# sheet.net
KiCad netlist of a schematic drawn in Altium Designer
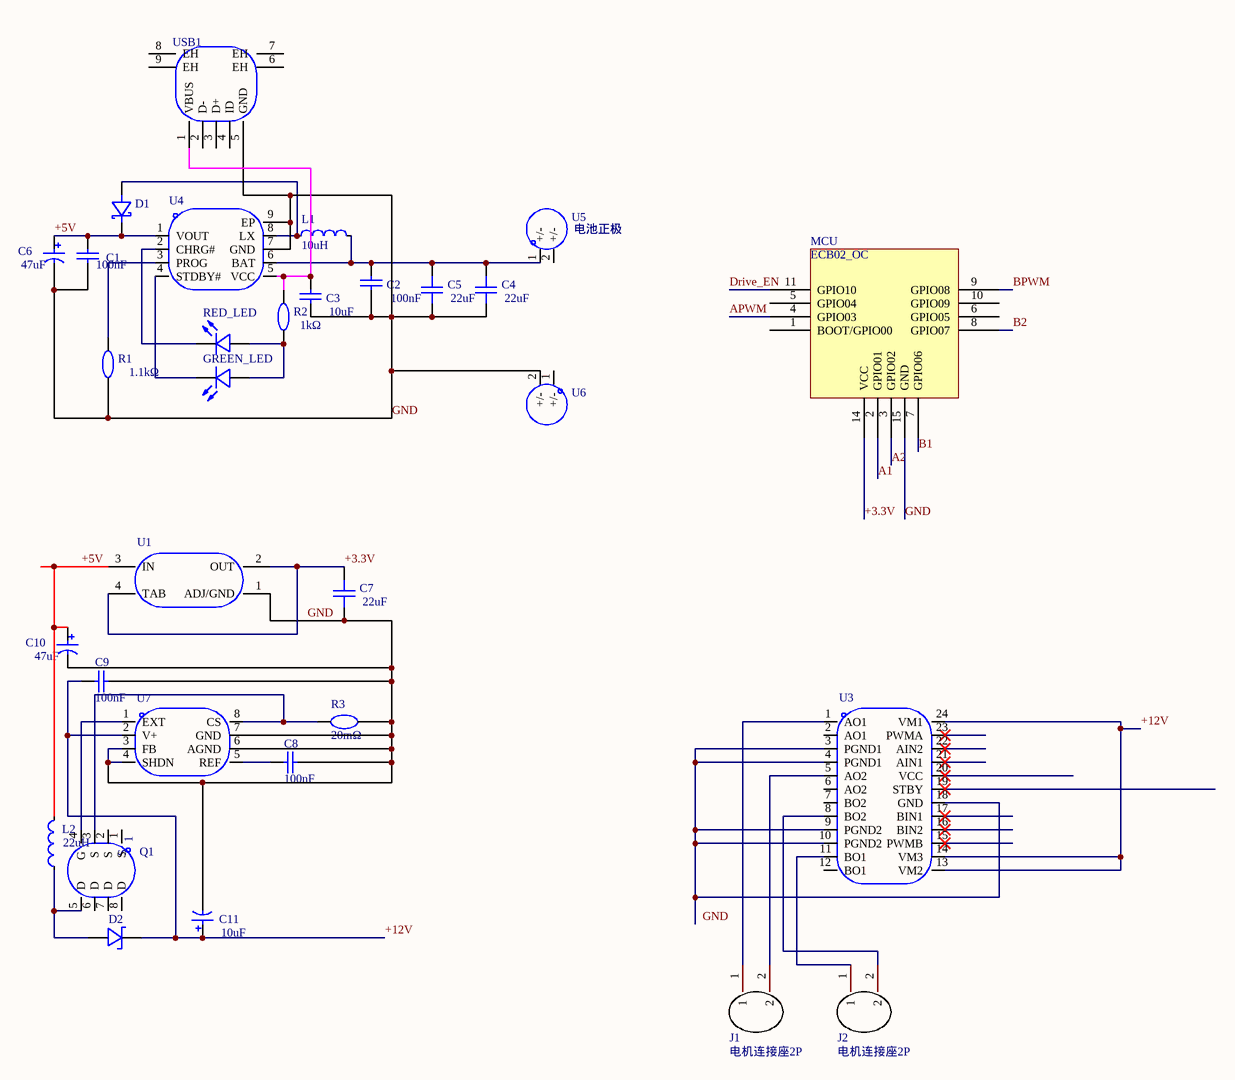
[diagram p0: sheet.schdoc]

(export (version "E")
  (design (tool "Eeschema 10.0.6"))
  (components
    (comp (ref "C1")
      (value "100nF")
      (footprint "C1206")
      (fields
        (field (name "MANUFACTURER") "FH(风华)")
        (field (name "MANUFACTURER PART") "1206B104K500NT")
        (field (name "TOLERANCE") "±10%")
      )
      (libsource (lib "altium-import") (part "root_1_1206B104K500NT_"))
    )
    (comp (ref "C2")
      (value "100nF")
      (footprint "C1206")
      (fields
        (field (name "MANUFACTURER") "FH(风华)")
        (field (name "MANUFACTURER PART") "1206B104K500NT")
        (field (name "TOLERANCE") "±10%")
      )
      (libsource (lib "altium-import") (part "root_1_1206B104K500NT_"))
    )
    (comp (ref "C3")
      (value "10uF")
      (footprint "C1206")
      (fields
        (field (name "MANUFACTURER") "SAMSUNG(三星)")
        (field (name "MANUFACTURER PART") "CL31B106KOHNNNE")
        (field (name "TOLERANCE") "±10%")
      )
      (libsource (lib "altium-import") (part "root_1_CL31B106KOHNNNE_"))
    )
    (comp (ref "C4")
      (value "22uF")
      (footprint "C1206")
      (fields
        (field (name "MANUFACTURER") "SAMSUNG(三星)")
        (field (name "MANUFACTURER PART") "CL31A226KOHNNNE")
        (field (name "TOLERANCE") "±10%")
      )
      (libsource (lib "altium-import") (part "root_1_CL31A226KOHNNNE_"))
    )
    (comp (ref "C5")
      (value "22uF")
      (footprint "C1206")
      (fields
        (field (name "MANUFACTURER") "SAMSUNG(三星)")
        (field (name "MANUFACTURER PART") "CL31A226KOHNNNE")
        (field (name "TOLERANCE") "±10%")
      )
      (libsource (lib "altium-import") (part "root_1_CL31A226KOHNNNE_"))
    )
    (comp (ref "C6")
      (value "47uF")
      (footprint "CAP-TH_BD5.0-P2.00-D0.8-FD")
      (fields
        (field (name "MANUFACTURER") "rubycon(红宝石)")
        (field (name "MANUFACTURER PART") "25YXF47MEFC5X11")
        (field (name "TOLERANCE") "±20%")
      )
      (libsource (lib "altium-import") (part "root_3_25YXF47MEFC5X11_"))
    )
    (comp (ref "C7")
      (value "22uF")
      (footprint "C1206")
      (fields
        (field (name "MANUFACTURER") "SAMSUNG(三星)")
        (field (name "MANUFACTURER PART") "CL31A226KOHNNNE")
        (field (name "TOLERANCE") "±10%")
      )
      (libsource (lib "altium-import") (part "root_1_CL31A226KOHNNNE_"))
    )
    (comp (ref "C8")
      (value "100nF")
      (footprint "C1206")
      (fields
        (field (name "MANUFACTURER") "FH(风华)")
        (field (name "MANUFACTURER PART") "1206B104K500NT")
        (field (name "TOLERANCE") "±10%")
      )
      (libsource (lib "altium-import") (part "root_2_1206B104K500NT_"))
    )
    (comp (ref "C9")
      (value "100nF")
      (footprint "C1206")
      (fields
        (field (name "MANUFACTURER") "FH(风华)")
        (field (name "MANUFACTURER PART") "1206B104K500NT")
        (field (name "TOLERANCE") "±10%")
      )
      (libsource (lib "altium-import") (part "root_2_1206B104K500NT_"))
    )
    (comp (ref "C10")
      (value "47uF")
      (footprint "CAP-TH_BD5.0-P2.00-D0.8-FD")
      (fields
        (field (name "MANUFACTURER") "rubycon(红宝石)")
        (field (name "MANUFACTURER PART") "25YXF47MEFC5X11")
        (field (name "TOLERANCE") "±20%")
      )
      (libsource (lib "altium-import") (part "root_3_25YXF47MEFC5X11_"))
    )
    (comp (ref "C11")
      (value "10uF")
      (footprint "CAP-TH_BD5.0-P2.00-D0.8-FD")
      (fields
        (field (name "MANUFACTURER") "rubycon(红宝石)")
        (field (name "MANUFACTURER PART") "50YXF10MEFC5X11")
        (field (name "TOLERANCE") "±20%")
      )
      (libsource (lib "altium-import") (part "root_1_50YXF10MEFC5X11_"))
    )
    (comp (ref "D1")
      (value "~")
      (footprint "SMA_L4.3-W2.6-LS5.1-RD")
      (fields (field (name "MANUFACTURER") "Slkor(萨科微)") (field (name "MANUFACTURER PART") "SS32"))
      (libsource (lib "altium-import") (part "root_1_SS32_C5122584_"))
    )
    (comp (ref "D2")
      (value "~")
      (footprint "SOD-323_L1.8-W1.3-LS2.5-RD")
      (fields (field (name "MANUFACTURER") "Hottech(合科泰)") (field (name "MANUFACTURER PART") "1N5819WS"))
      (libsource (lib "altium-import") (part "root_2_1N5819WS_C191023_"))
    )
    (comp (ref "GREEN_LED")
      (value "~")
      (footprint "LED0805-R-RD")
      (fields (field (name "MANUFACTURER") "国星光电") (field (name "MANUFACTURER PART") "NCD0805G1"))
      (libsource (lib "altium-import") (part "root_2_NCD0805G1_"))
    )
    (comp (ref "J1") (value "电机连接座2P") (footprint "电机连接座2P") (libsource (lib "1_P1") (part "电机连接座2P")))
    (comp (ref "J2") (value "电机连接座2P") (footprint "电机连接座2P") (libsource (lib "1_P1") (part "电机连接座2P")))
    (comp (ref "L1")
      (value "10uH")
      (footprint "IND-SMD_L4.4-W4.2")
      (fields
        (field (name "MANUFACTURER") "cjiang(长江微电)")
        (field (name "MANUFACTURER PART") "FXL0420-100-M")
        (field (name "TOLERANCE") "±20%")
      )
      (libsource (lib "altium-import") (part "root_0_FXL0420-100-M_"))
    )
    (comp (ref "L2")
      (value "22uH")
      (footprint "IND-SMD_L6.0-W6.0_SWPA6045S")
      (fields
        (field (name "MANUFACTURER") "Sunlord(顺络)")
        (field (name "MANUFACTURER PART") "SWPA6045S220MT")
        (field (name "TOLERANCE") "±20%")
      )
      (libsource (lib "altium-import") (part "root_1_SWPA6045S220MT_"))
    )
    (comp (ref "MCU") (value "ECB02_OC") (footprint "ECB02_OC") (libsource (lib "1_P1") (part "ECB02_OC")))
    (comp (ref "Q1")
      (value "~")
      (footprint "SO-8_L4.9-W3.9-P1.27-LS5.9-BL")
      (fields
        (field (name "MANUFACTURER") "VBsemi(台湾微碧)")
        (field (name "MANUFACTURER PART") "SI9410BDY-T1")
        (field (name "NAME") "S")
        (field (name "NUMBER") "1")
      )
      (libsource (lib "altium-import") (part "root_3_SI9410BDY-T1_"))
    )
    (comp (ref "R1")
      (value "1.1kΩ")
      (footprint "R1206")
      (fields
        (field (name "MANUFACTURER") "RESI(开步睿思）")
        (field (name "MANUFACTURER PART") "AECR1206F1K10K9")
        (field (name "TOLERANCE") "±1%")
      )
      (libsource (lib "altium-import") (part "root_1_AECR1206F1K10K9_"))
    )
    (comp (ref "R2")
      (value "1kΩ")
      (footprint "R1206")
      (fields
        (field (name "MANUFACTURER") "UNI-ROYAL(厚声)")
        (field (name "MANUFACTURER PART") "1206W4J0102T5E")
        (field (name "TOLERANCE") "±5%")
      )
      (libsource (lib "altium-import") (part "root_1_1206W4J0102T5E_"))
    )
    (comp (ref "R3")
      (value "20mΩ")
      (footprint "R1206")
      (fields
        (field (name "MANUFACTURER") "UNI-ROYAL(厚声)")
        (field (name "MANUFACTURER PART") "1206W3F200MT5E")
        (field (name "TOLERANCE") "±1%")
      )
      (libsource (lib "altium-import") (part "root_0_1206W3F200MT5E_"))
    )
    (comp (ref "RED_LED")
      (value "~")
      (footprint "LED0805-RD_RED")
      (fields (field (name "MANUFACTURER") "国星光电") (field (name "MANUFACTURER PART") "NCD0805R1"))
      (libsource (lib "altium-import") (part "root_0_NCD0805R1_"))
    )
    (comp (ref "U1")
      (value "~")
      (footprint "TO-263-3L_L10.0-W9.2-P2.54-TL")
      (fields (field (name "MANUFACTURER") "HTC") (field (name "MANUFACTURER PART") "LM1085R-3.3"))
      (libsource (lib "altium-import") (part "root_0_LM1085R-3.3_"))
    )
    (comp (ref "U3")
      (value "~")
      (footprint "SSOP-24_L8.4-W5.8-P0.65-LS7.8-BL")
      (fields
        (field (name "MANUFACTURER") "TOSHIBA(东芝)")
        (field (name "MANUFACTURER PART") "TB6612FNG(O,C,8,EL")
      )
      (libsource (lib "altium-import") (part "root_0_TB6612FNG(O,C,8,EL_"))
    )
    (comp (ref "U4")
      (value "~")
      (footprint "ESOP-8_L4.9-W3.9-P1.27-LS6.0-BL-EP")
      (fields (field (name "MANUFACTURER") "TOPPOWER(南京拓微)") (field (name "MANUFACTURER PART") "TP5400"))
      (libsource (lib "altium-import") (part "root_0_TP5400_"))
    )
    (comp (ref "U5")
      (value "电池正极")
      (footprint "BAT-SMD_MY-18650-02")
      (fields
        (field (name "NAME") "电池正极")
        (field (name "MANUFACTURER") "MYOUNG(美阳)")
        (field (name "MANUFACTURER PART") "MY-18650-02")
      )
      (libsource (lib "altium-import") (part "root_1_MY-18650-02_"))
    )
    (comp (ref "U6")
      (value "电池负极")
      (footprint "BAT-SMD_MY-18650-02")
      (fields (field (name "MANUFACTURER") "MYOUNG(美阳)") (field (name "MANUFACTURER PART") "MY-18650-02"))
      (libsource (lib "altium-import") (part "root_3_MY-18650-02_"))
    )
    (comp (ref "U7")
      (value "~")
      (footprint "SO-8_L4.9-W3.9-P1.27-LS6.0-BL")
      (fields (field (name "MANUFACTURER") "MAXIM(美信)") (field (name "MANUFACTURER PART") "MAX1771ESA+T"))
      (libsource (lib "altium-import") (part "root_0_MAX1771ESA+T_"))
    )
    (comp (ref "USB1")
      (value "~")
      (footprint "MICRO-USB-SMD_KH-MICRO-SMT.ZJ-5P")
      (fields
        (field (name "MANUFACTURER") "kinghelm(金航标)")
        (field (name "MANUFACTURER PART") "KH-MICRO-SMT.ZJ-5P")
      )
      (libsource (lib "altium-import") (part "root_1_KH-MICRO-SMT.ZJ-5P_"))
    )
  )
  (nets
    (net (code "1") (name "/+3.3V") (class "Default")
      (node (ref "C7") (pin "2") (pinfunction "2_2") (pintype "passive"))
      (node (ref "MCU") (pin "14") (pinfunction "VCC_14") (pintype "passive"))
      (node (ref "U1") (pin "2") (pinfunction "OUT_2") (pintype "passive"))
      (node (ref "U1") (pin "4") (pinfunction "TAB_4") (pintype "passive"))
    )
    (net (code "2") (name "/+5V") (class "Default")
      (node (ref "C1") (pin "2") (pinfunction "2_2") (pintype "passive"))
      (node (ref "C10") (pin "1") (pinfunction "1_1") (pintype "passive"))
      (node (ref "C6") (pin "1") (pinfunction "1_1") (pintype "passive"))
      (node (ref "D1") (pin "1") (pinfunction "1_1") (pintype "passive"))
      (node (ref "L2") (pin "2") (pinfunction "2_2") (pintype "passive"))
      (node (ref "U1") (pin "3") (pinfunction "IN_3") (pintype "passive"))
      (node (ref "U4") (pin "1") (pinfunction "VOUT_1") (pintype "passive"))
    )
    (net (code "3") (name "/+12V") (class "Default")
      (node (ref "C11") (pin "1") (pinfunction "1_1") (pintype "passive"))
      (node (ref "C9") (pin "2") (pinfunction "2_2") (pintype "passive"))
      (node (ref "D2") (pin "1") (pinfunction "C_1") (pintype "passive"))
      (node (ref "U3") (pin "13") (pinfunction "VM2_13") (pintype "passive"))
      (node (ref "U3") (pin "14") (pinfunction "VM3_14") (pintype "passive"))
      (node (ref "U3") (pin "24") (pinfunction "VM1_24") (pintype "passive"))
      (node (ref "U7") (pin "2") (pinfunction "V+_2") (pintype "passive"))
    )
    (net (code "4") (name "/A1") (class "Default")
      (node (ref "MCU") (pin "2") (pinfunction "GPIO01_2") (pintype "passive"))
    )
    (net (code "5") (name "/A2") (class "Default")
      (node (ref "MCU") (pin "3") (pinfunction "GPIO02_3") (pintype "passive"))
    )
    (net (code "6") (name "/APWM") (class "Default")
      (node (ref "MCU") (pin "4") (pinfunction "GPIO03_4") (pintype "passive"))
    )
    (net (code "7") (name "/B1") (class "Default")
      (node (ref "MCU") (pin "7") (pinfunction "GPIO06_7") (pintype "passive"))
    )
    (net (code "8") (name "/B2") (class "Default")
      (node (ref "MCU") (pin "8") (pinfunction "GPIO07_8") (pintype "passive"))
    )
    (net (code "9") (name "/BPWM") (class "Default")
      (node (ref "MCU") (pin "9") (pinfunction "GPIO08_9") (pintype "passive"))
    )
    (net (code "10") (name "/Drive_EN") (class "Default")
      (node (ref "MCU") (pin "11") (pinfunction "GPIO10_11") (pintype "passive"))
    )
    (net (code "11") (name "/GND") (class "Default")
      (node (ref "C1") (pin "1") (pinfunction "1_1") (pintype "passive"))
      (node (ref "C10") (pin "2") (pinfunction "2_2") (pintype "passive"))
      (node (ref "C11") (pin "2") (pinfunction "2_2") (pintype "passive"))
      (node (ref "C2") (pin "1") (pinfunction "1_1") (pintype "passive"))
      (node (ref "C3") (pin "1") (pinfunction "1_1") (pintype "passive"))
      (node (ref "C4") (pin "1") (pinfunction "1_1") (pintype "passive"))
      (node (ref "C5") (pin "1") (pinfunction "1_1") (pintype "passive"))
      (node (ref "C6") (pin "2") (pinfunction "2_2") (pintype "passive"))
      (node (ref "C7") (pin "1") (pinfunction "1_1") (pintype "passive"))
      (node (ref "C8") (pin "1") (pinfunction "1_1") (pintype "passive"))
      (node (ref "C9") (pin "1") (pinfunction "1_1") (pintype "passive"))
      (node (ref "MCU") (pin "15") (pinfunction "GND_15") (pintype "passive"))
      (node (ref "R1") (pin "1") (pinfunction "1_1") (pintype "passive"))
      (node (ref "R3") (pin "2") (pinfunction "2_2") (pintype "passive"))
      (node (ref "U1") (pin "1") (pinfunction "ADJ/GND_1") (pintype "passive"))
      (node (ref "U4") (pin "7") (pinfunction "GND_7") (pintype "passive"))
      (node (ref "U4") (pin "9") (pinfunction "EP_9") (pintype "passive"))
      (node (ref "U6") (pin "2") (pinfunction "+/-_2") (pintype "passive"))
      (node (ref "U7") (pin "3") (pinfunction "FB_3") (pintype "passive"))
      (node (ref "U7") (pin "4") (pinfunction "SHDN_4") (pintype "passive"))
      (node (ref "U7") (pin "6") (pinfunction "AGND_6") (pintype "passive"))
      (node (ref "U7") (pin "7") (pinfunction "GND_7") (pintype "passive"))
      (node (ref "USB1") (pin "5") (pinfunction "GND_5") (pintype "passive"))
    )
    (net (code "12") (name "Net-(D2-A)") (class "Default")
      (node (ref "D2") (pin "2") (pinfunction "A_2") (pintype "passive"))
      (node (ref "L2") (pin "1") (pinfunction "1_1") (pintype "passive"))
      (node (ref "Q1") (pin "5") (pinfunction "D_5") (pintype "passive"))
    )
    (net (code "13") (name "Net-(GREEN_LED-A)") (class "Default")
      (node (ref "GREEN_LED") (pin "1") (pinfunction "A_1") (pintype "passive"))
      (node (ref "R2") (pin "1") (pinfunction "1_1") (pintype "passive"))
      (node (ref "RED_LED") (pin "2") (pinfunction "+_2") (pintype "passive"))
    )
    (net (code "14") (name "Net-(GREEN_LED-K)") (class "Default")
      (node (ref "GREEN_LED") (pin "2") (pinfunction "K_2") (pintype "passive"))
      (node (ref "U4") (pin "4") (pinfunction "STDBY#_4") (pintype "passive"))
    )
    (net (code "15") (name "Net-(J1-Pad1)") (class "Default")
      (node (ref "J1") (pin "1") (pinfunction "1_1") (pintype "passive"))
      (node (ref "U3") (pin "1") (pinfunction "AO1_1") (pintype "passive"))
    )
    (net (code "16") (name "Net-(J1-Pad2)") (class "Default")
      (node (ref "J1") (pin "2") (pinfunction "2_2") (pintype "passive"))
      (node (ref "U3") (pin "5") (pinfunction "AO2_5") (pintype "passive"))
    )
    (net (code "17") (name "Net-(J2-Pad1)") (class "Default")
      (node (ref "J2") (pin "1") (pinfunction "1_1") (pintype "passive"))
      (node (ref "U3") (pin "11") (pinfunction "BO1_11") (pintype "passive"))
    )
    (net (code "18") (name "Net-(J2-Pad2)") (class "Default")
      (node (ref "J2") (pin "2") (pinfunction "2_2") (pintype "passive"))
      (node (ref "U3") (pin "8") (pinfunction "BO2_8") (pintype "passive"))
    )
    (net (code "19") (name "Net-(Q1-G)") (class "Default")
      (node (ref "Q1") (pin "4") (pinfunction "G_4") (pintype "passive"))
      (node (ref "U7") (pin "1") (pinfunction "EXT_1") (pintype "passive"))
    )
    (net (code "20") (name "Net-(RED_LED--)") (class "Default")
      (node (ref "RED_LED") (pin "1") (pinfunction "-_1") (pintype "passive"))
      (node (ref "U4") (pin "2") (pinfunction "CHRG#_2") (pintype "passive"))
    )
    (net (code "21") (name "Net-(U3-GND)") (class "Default")
      (node (ref "U3") (pin "10") (pinfunction "PGND2_10") (pintype "passive"))
      (node (ref "U3") (pin "18") (pinfunction "GND_18") (pintype "passive"))
      (node (ref "U3") (pin "3") (pinfunction "PGND1_3") (pintype "passive"))
      (node (ref "U3") (pin "4") (pinfunction "PGND1_4") (pintype "passive"))
      (node (ref "U3") (pin "9") (pinfunction "PGND2_9") (pintype "passive"))
    )
    (net (code "22") (name "Net-(U4-BAT)") (class "Default")
      (node (ref "C2") (pin "2") (pinfunction "2_2") (pintype "passive"))
      (node (ref "C4") (pin "2") (pinfunction "2_2") (pintype "passive"))
      (node (ref "C5") (pin "2") (pinfunction "2_2") (pintype "passive"))
      (node (ref "L1") (pin "2") (pinfunction "2_2") (pintype "passive"))
      (node (ref "U4") (pin "6") (pinfunction "BAT_6") (pintype "passive"))
      (node (ref "U5") (pin "1") (pinfunction "+/-_1") (pintype "passive"))
    )
    (net (code "23") (name "Net-(U4-LX)") (class "Default")
      (node (ref "D1") (pin "2") (pinfunction "2_2") (pintype "passive"))
      (node (ref "L1") (pin "1") (pinfunction "1_1") (pintype "passive"))
      (node (ref "U4") (pin "8") (pinfunction "LX_8") (pintype "passive"))
    )
    (net (code "24") (name "Net-(U4-PROG)") (class "Default")
      (node (ref "R1") (pin "2") (pinfunction "2_2") (pintype "passive"))
      (node (ref "U4") (pin "3") (pinfunction "PROG_3") (pintype "passive"))
    )
    (net (code "25") (name "Net-(U4-VCC)") (class "Default")
      (node (ref "C3") (pin "2") (pinfunction "2_2") (pintype "passive"))
      (node (ref "R2") (pin "2") (pinfunction "2_2") (pintype "passive"))
      (node (ref "U4") (pin "5") (pinfunction "VCC_5") (pintype "passive"))
      (node (ref "USB1") (pin "1") (pinfunction "VBUS_1") (pintype "passive"))
    )
    (net (code "26") (name "Net-(U7-CS)") (class "Default")
      (node (ref "Q1") (pin "3") (pinfunction "S_3") (pintype "passive"))
      (node (ref "R3") (pin "1") (pinfunction "1_1") (pintype "passive"))
      (node (ref "U7") (pin "8") (pinfunction "CS_8") (pintype "passive"))
    )
    (net (code "27") (name "Net-(U7-REF)") (class "Default")
      (node (ref "C8") (pin "2") (pinfunction "2_2") (pintype "passive"))
      (node (ref "U7") (pin "5") (pinfunction "REF_5") (pintype "passive"))
    )
    (net (code "28") (name "unconnected-(MCU-BOOT{slash}GPIO00-Pad1)") (class "Default")
      (node (ref "MCU") (pin "1") (pinfunction "BOOT/GPIO00_1") (pintype "passive"))
    )
    (net (code "29") (name "unconnected-(MCU-GPIO04-Pad5)") (class "Default")
      (node (ref "MCU") (pin "5") (pinfunction "GPIO04_5") (pintype "passive"))
    )
    (net (code "30") (name "unconnected-(MCU-GPIO05-Pad6)") (class "Default")
      (node (ref "MCU") (pin "6") (pinfunction "GPIO05_6") (pintype "passive"))
    )
    (net (code "31") (name "unconnected-(MCU-GPIO09-Pad10)") (class "Default")
      (node (ref "MCU") (pin "10") (pinfunction "GPIO09_10") (pintype "passive"))
    )
    (net (code "32") (name "unconnected-(Q1-D-Pad6)") (class "Default")
      (node (ref "Q1") (pin "6") (pinfunction "D_6") (pintype "passive"))
    )
    (net (code "33") (name "unconnected-(Q1-D-Pad7)") (class "Default")
      (node (ref "Q1") (pin "7") (pinfunction "D_7") (pintype "passive"))
    )
    (net (code "34") (name "unconnected-(Q1-D-Pad8)") (class "Default")
      (node (ref "Q1") (pin "8") (pinfunction "D_8") (pintype "passive"))
    )
    (net (code "35") (name "unconnected-(Q1-S-Pad1)") (class "Default")
      (node (ref "Q1") (pin "1") (pinfunction "S_1") (pintype "passive"))
    )
    (net (code "36") (name "unconnected-(Q1-S-Pad2)") (class "Default")
      (node (ref "Q1") (pin "2") (pinfunction "S_2") (pintype "passive"))
    )
    (net (code "37") (name "unconnected-(U3-AIN1-Pad21)") (class "Default")
      (node (ref "U3") (pin "21") (pinfunction "AIN1_21") (pintype "passive+no_connect"))
    )
    (net (code "38") (name "unconnected-(U3-AIN2-Pad22)") (class "Default")
      (node (ref "U3") (pin "22") (pinfunction "AIN2_22") (pintype "passive+no_connect"))
    )
    (net (code "39") (name "unconnected-(U3-AO1-Pad2)") (class "Default")
      (node (ref "U3") (pin "2") (pinfunction "AO1_2") (pintype "passive"))
    )
    (net (code "40") (name "unconnected-(U3-AO2-Pad6)") (class "Default")
      (node (ref "U3") (pin "6") (pinfunction "AO2_6") (pintype "passive"))
    )
    (net (code "41") (name "unconnected-(U3-BIN1-Pad17)") (class "Default")
      (node (ref "U3") (pin "17") (pinfunction "BIN1_17") (pintype "passive+no_connect"))
    )
    (net (code "42") (name "unconnected-(U3-BIN2-Pad16)") (class "Default")
      (node (ref "U3") (pin "16") (pinfunction "BIN2_16") (pintype "passive+no_connect"))
    )
    (net (code "43") (name "unconnected-(U3-BO1-Pad12)") (class "Default")
      (node (ref "U3") (pin "12") (pinfunction "BO1_12") (pintype "passive"))
    )
    (net (code "44") (name "unconnected-(U3-BO2-Pad7)") (class "Default")
      (node (ref "U3") (pin "7") (pinfunction "BO2_7") (pintype "passive"))
    )
    (net (code "45") (name "unconnected-(U3-PWMA-Pad23)") (class "Default")
      (node (ref "U3") (pin "23") (pinfunction "PWMA_23") (pintype "passive+no_connect"))
    )
    (net (code "46") (name "unconnected-(U3-PWMB-Pad15)") (class "Default")
      (node (ref "U3") (pin "15") (pinfunction "PWMB_15") (pintype "passive+no_connect"))
    )
    (net (code "47") (name "unconnected-(U3-STBY-Pad19)") (class "Default")
      (node (ref "U3") (pin "19") (pinfunction "STBY_19") (pintype "passive+no_connect"))
    )
    (net (code "48") (name "unconnected-(U3-VCC-Pad20)") (class "Default")
      (node (ref "U3") (pin "20") (pinfunction "VCC_20") (pintype "passive+no_connect"))
    )
    (net (code "49") (name "unconnected-(U5-+{slash}--Pad2)") (class "Default")
      (node (ref "U5") (pin "2") (pinfunction "+/-_2") (pintype "passive"))
    )
    (net (code "50") (name "unconnected-(U6-+{slash}--Pad1)") (class "Default")
      (node (ref "U6") (pin "1") (pinfunction "+/-_1") (pintype "passive"))
    )
    (net (code "51") (name "unconnected-(USB1-D+-Pad3)") (class "Default")
      (node (ref "USB1") (pin "3") (pinfunction "D+_3") (pintype "passive"))
    )
    (net (code "52") (name "unconnected-(USB1-D--Pad2)") (class "Default")
      (node (ref "USB1") (pin "2") (pinfunction "D-_2") (pintype "passive"))
    )
    (net (code "53") (name "unconnected-(USB1-EH-Pad6)") (class "Default")
      (node (ref "USB1") (pin "6") (pinfunction "EH_6") (pintype "passive"))
    )
    (net (code "54") (name "unconnected-(USB1-EH-Pad7)") (class "Default")
      (node (ref "USB1") (pin "7") (pinfunction "EH_7") (pintype "passive"))
    )
    (net (code "55") (name "unconnected-(USB1-EH-Pad8)") (class "Default")
      (node (ref "USB1") (pin "8") (pinfunction "EH_8") (pintype "passive"))
    )
    (net (code "56") (name "unconnected-(USB1-EH-Pad9)") (class "Default")
      (node (ref "USB1") (pin "9") (pinfunction "EH_9") (pintype "passive"))
    )
    (net (code "57") (name "unconnected-(USB1-ID-Pad4)") (class "Default")
      (node (ref "USB1") (pin "4") (pinfunction "ID_4") (pintype "passive"))
    )
  )
)
